# NODE_1_SCH.net
KiCad netlist of a schematic drawn in Altium Designer
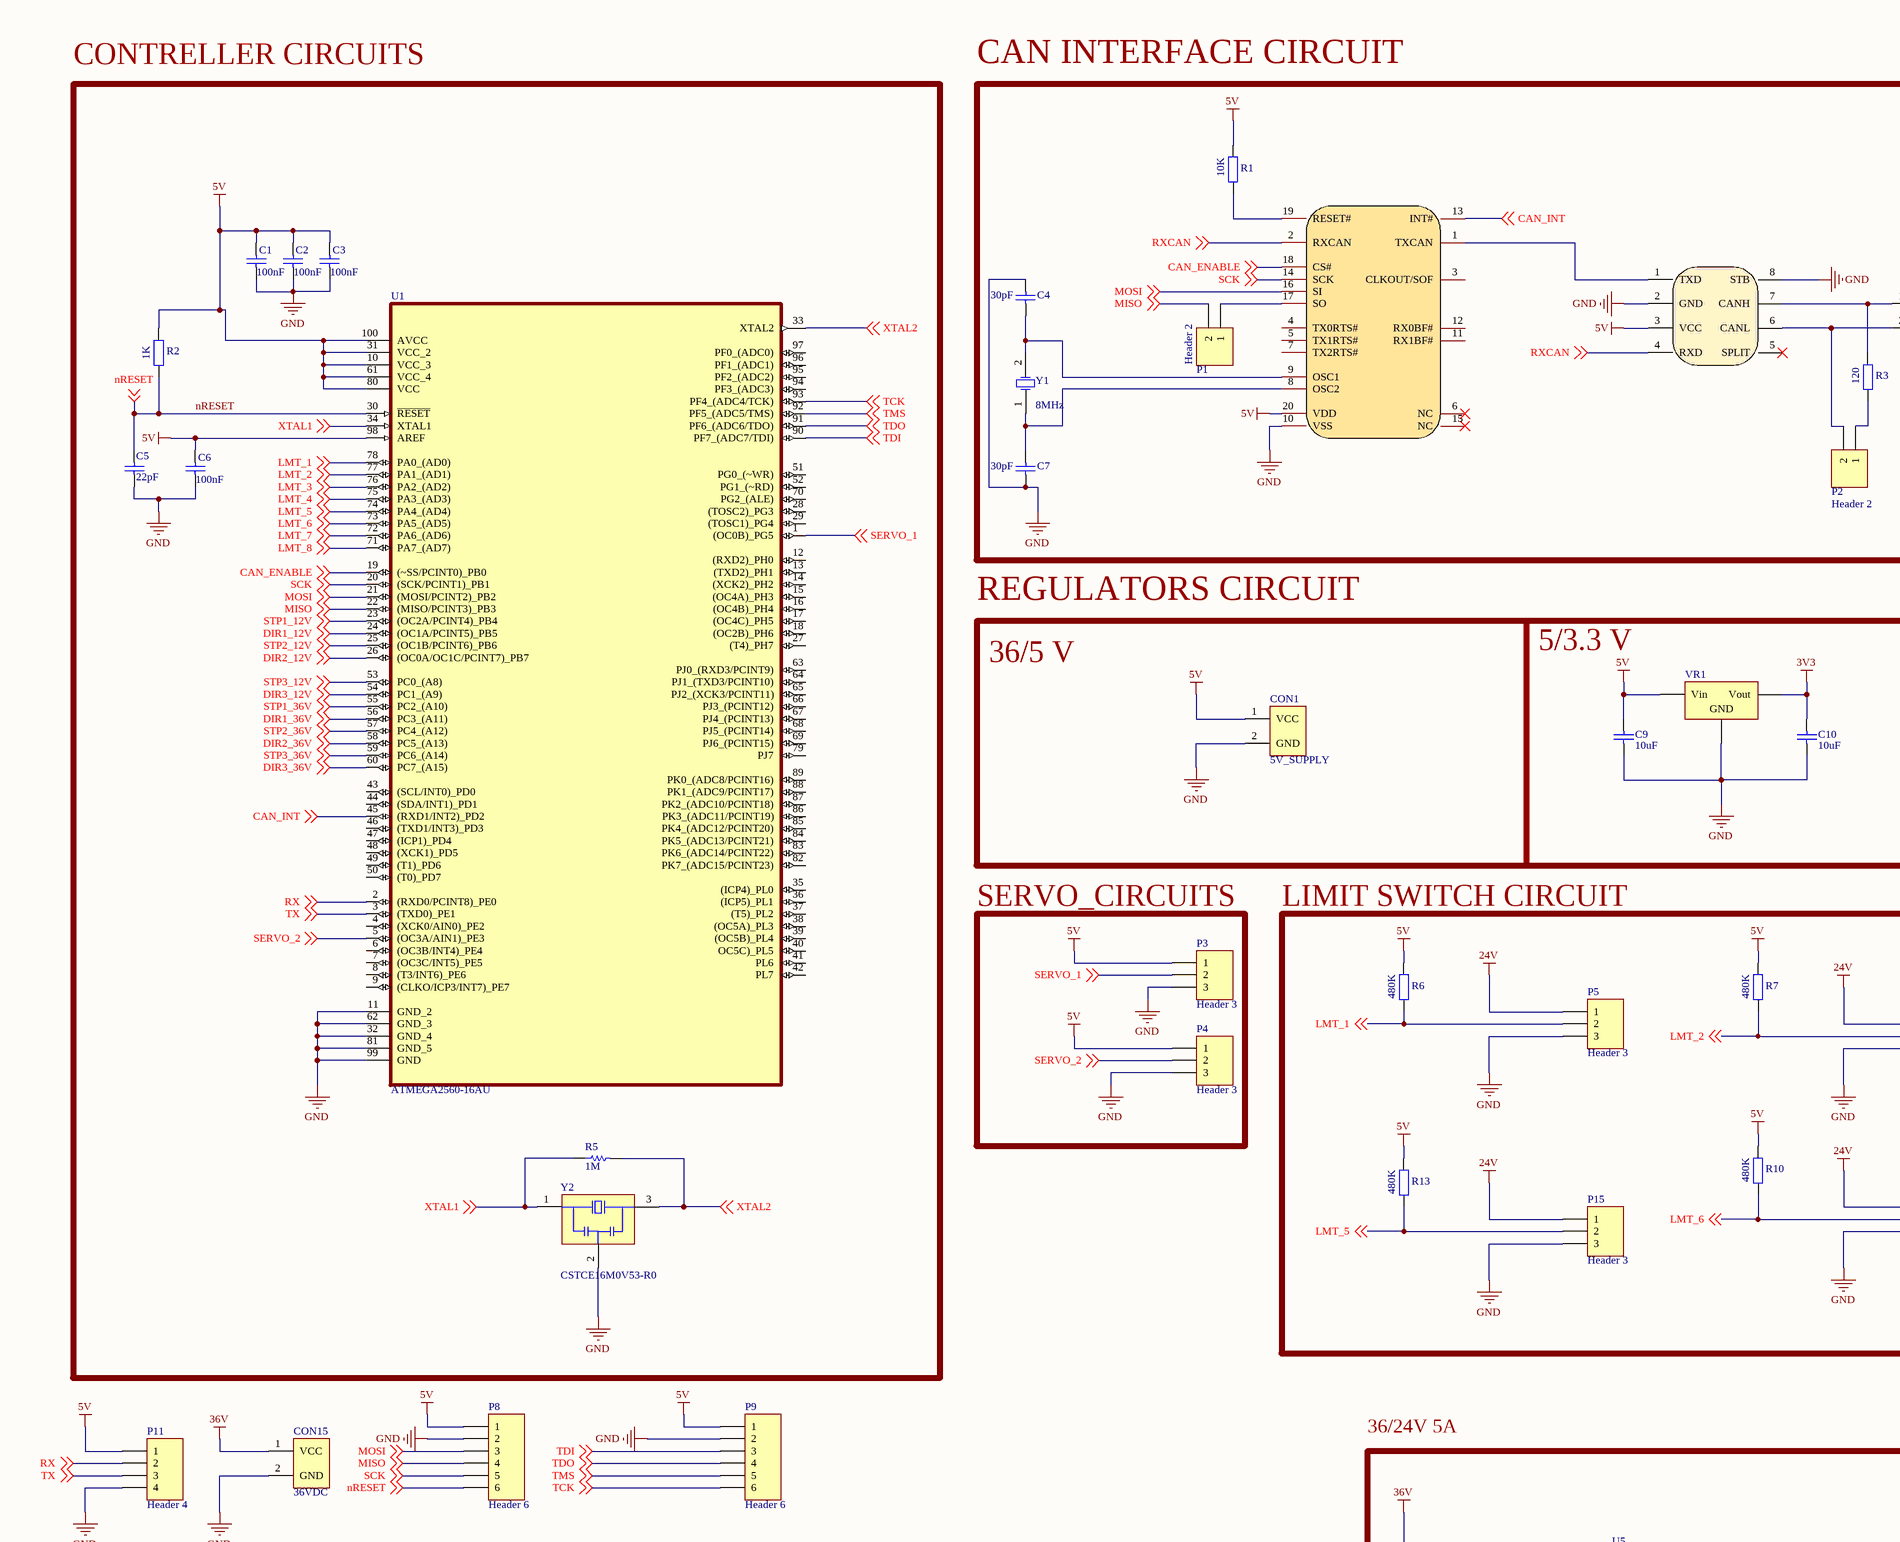
[diagram p0: NODE_1_SCH.SchDoc, top left]
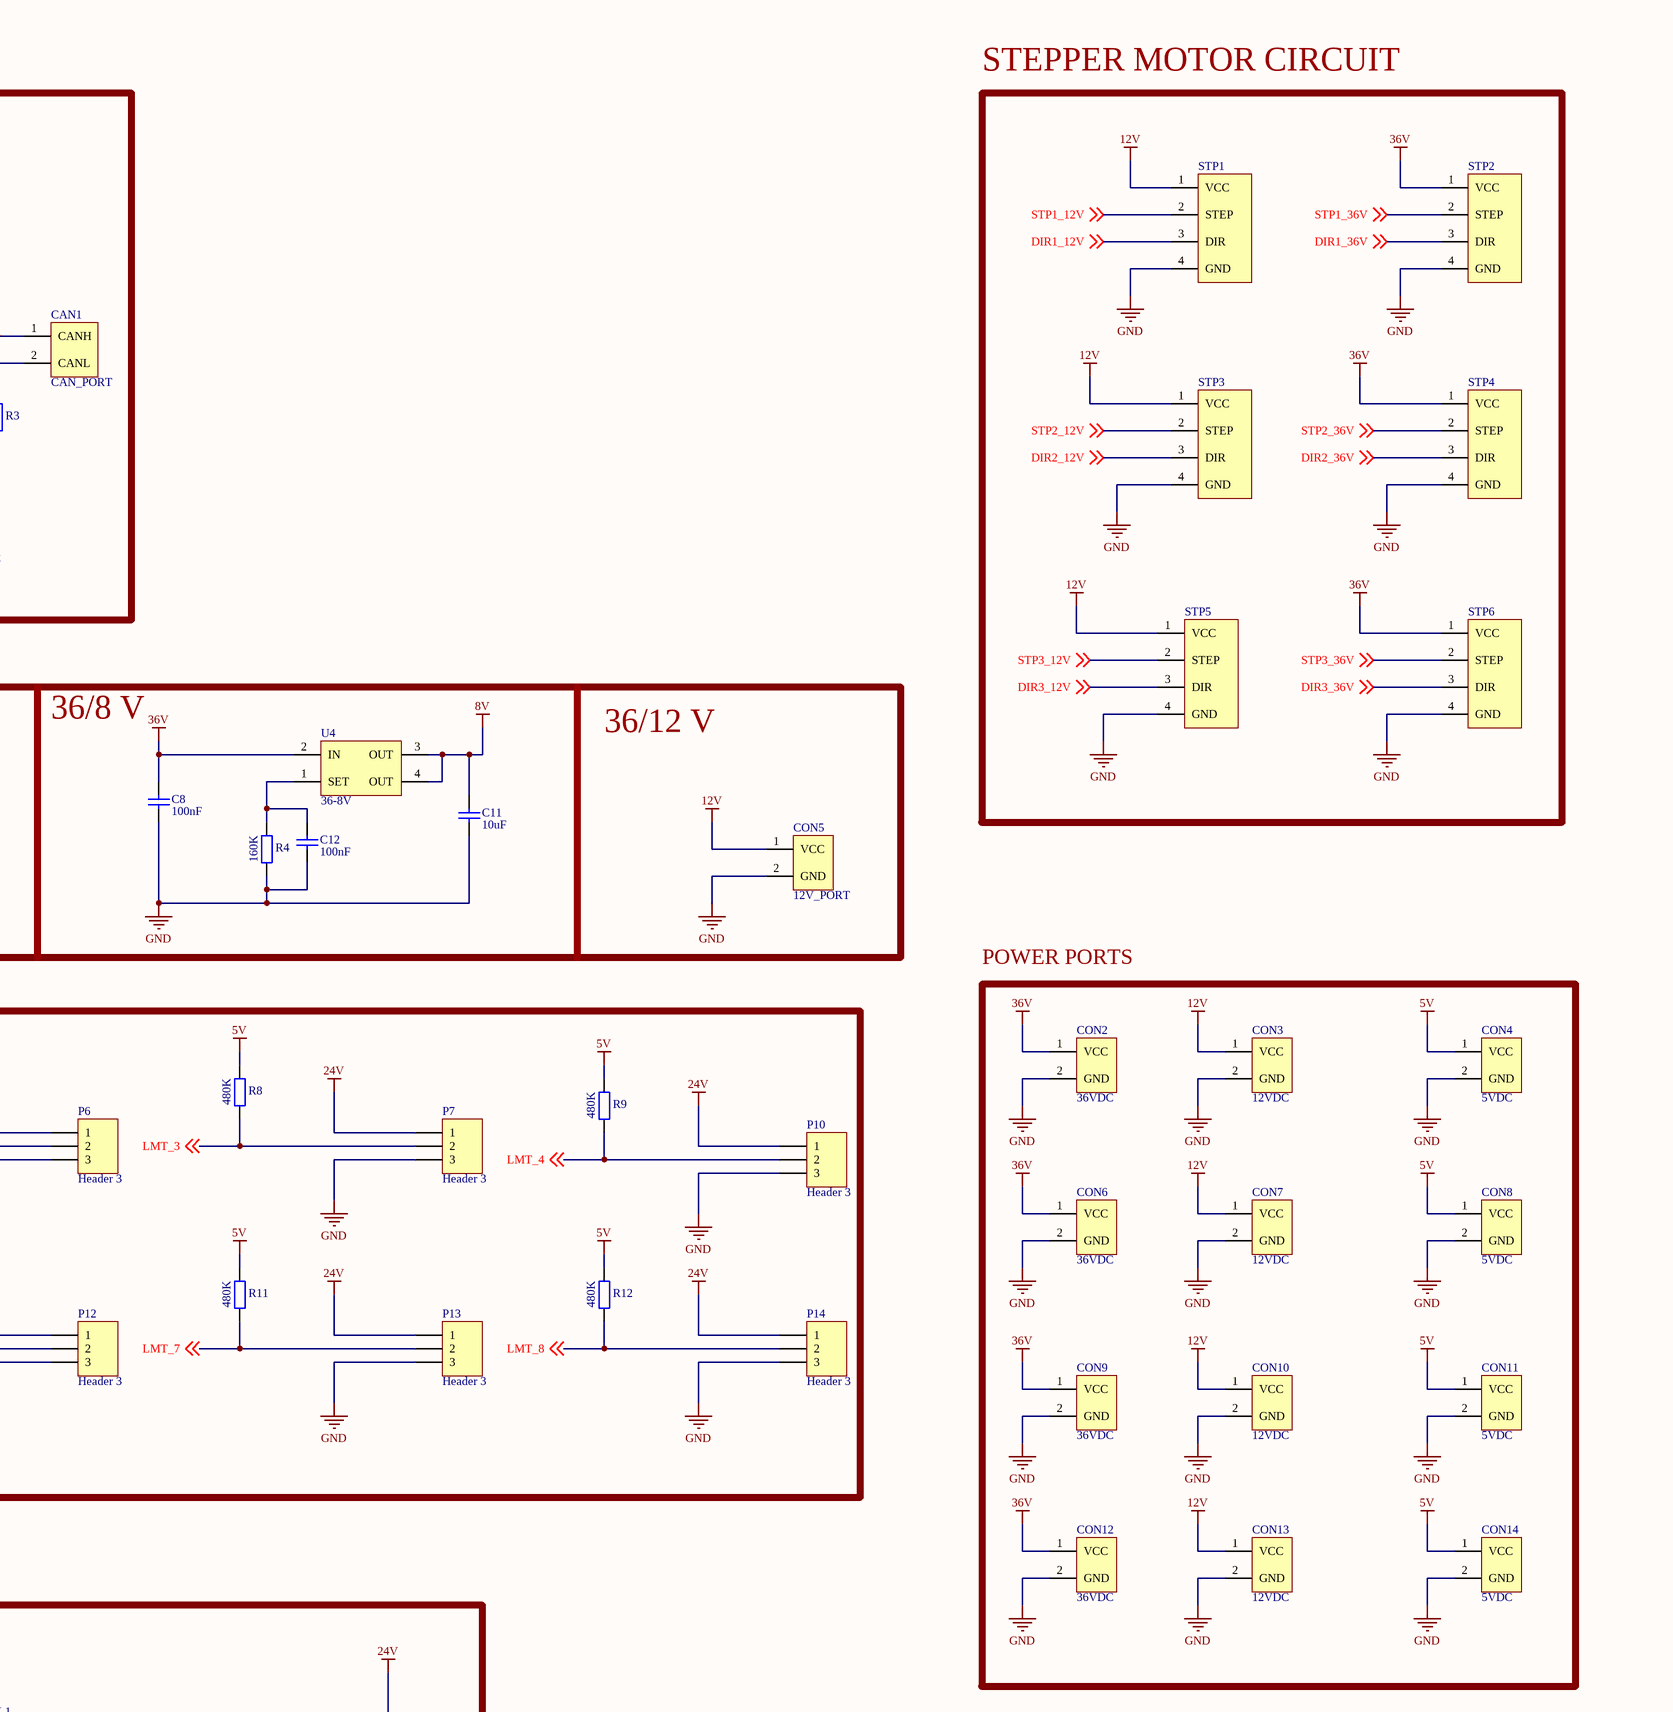
[diagram p1: NODE_1_SCH.SchDoc, top right]
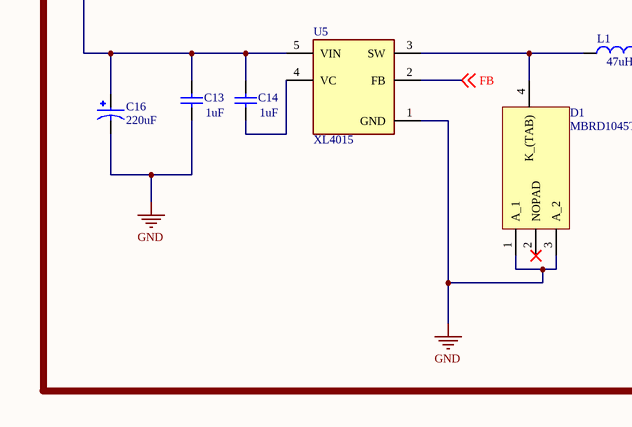
[diagram p2: NODE_1_SCH.SchDoc, bottom left]
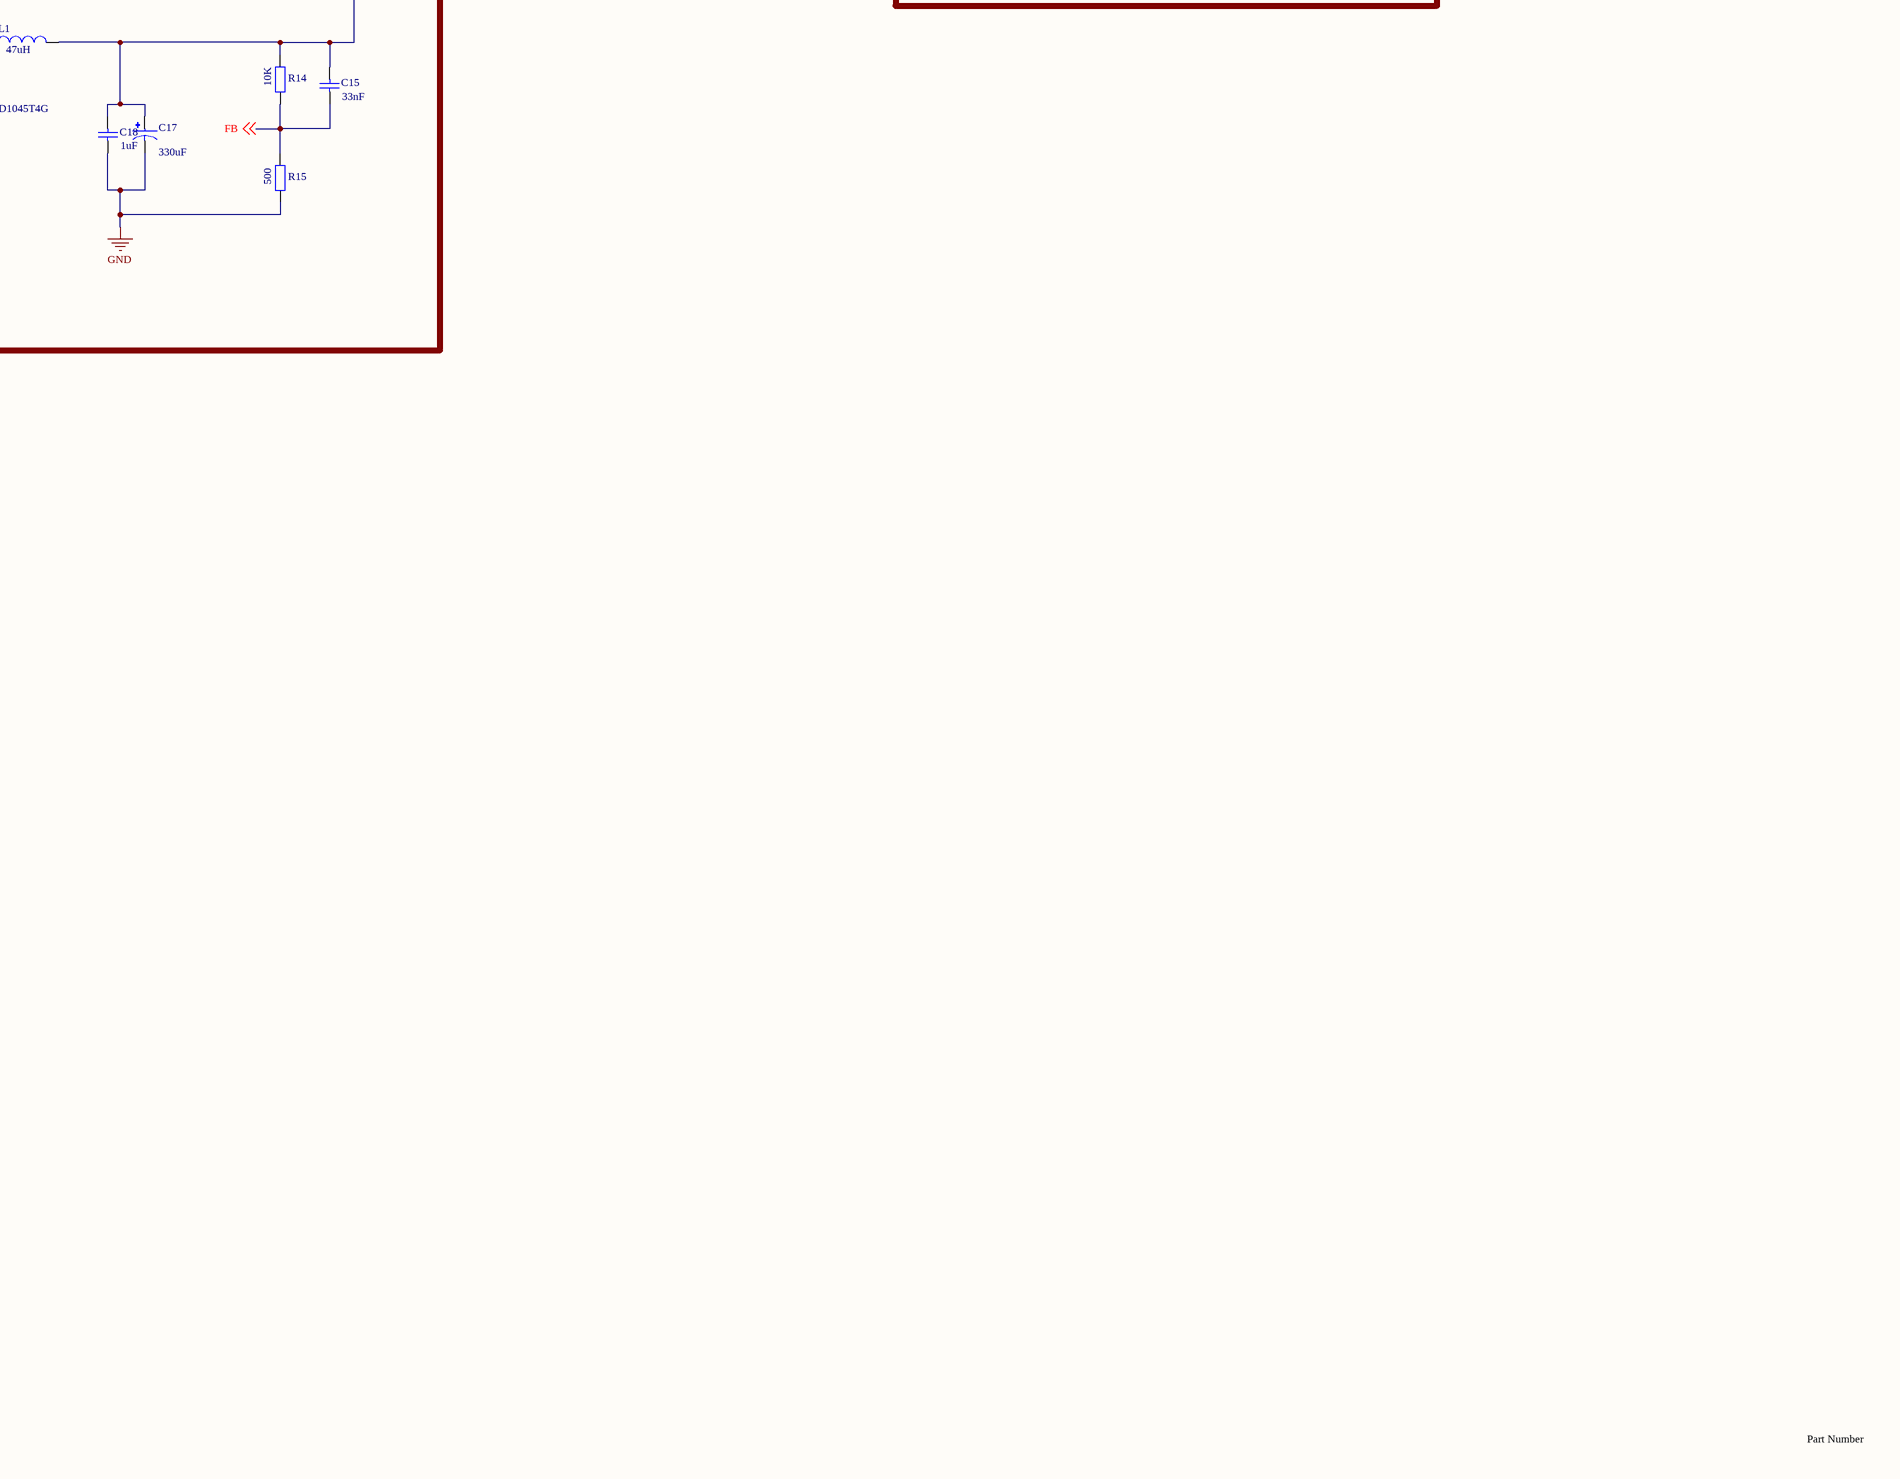
[diagram p3: NODE_1_SCH.SchDoc, bottom right]

(export (version "E")
  (design (tool "Eeschema 10.0.6"))
  (components
    (comp (ref "C1")
      (value "100nF")
      (footprint "CAPC2012X135N")
      (description "Capacitor")
      (fields
        (field (name "PART NUMBER") "TCC0805X7R104M500DT")
        (field (name "Comment") "Cap")
        (field (name "PUBLISHER") "Altium Limited")
      )
      (libsource (lib "Miscellaneous Devices") (part "Cap"))
    )
    (comp (ref "C2")
      (value "100nF")
      (footprint "CAPC2012X135N")
      (description "Capacitor")
      (fields
        (field (name "PART NUMBER") "TCC0805X7R104M500DT")
        (field (name "Comment") "Cap")
        (field (name "PUBLISHER") "Altium Limited")
      )
      (libsource (lib "Miscellaneous Devices") (part "Cap"))
    )
    (comp (ref "C3")
      (value "100nF")
      (footprint "CAPC2012X135N")
      (description "Capacitor")
      (fields
        (field (name "PART NUMBER") "TCC0805X7R104M500DT")
        (field (name "Comment") "Cap")
        (field (name "PUBLISHER") "Altium Limited")
      )
      (libsource (lib "Miscellaneous Devices") (part "Cap"))
    )
    (comp (ref "C4")
      (value "30pF")
      (footprint "CAPC2012X135N")
      (description "Capacitor")
      (fields
        (field (name "PART NUMBER") "TCC0805COG300J500BT")
        (field (name "Comment") "Cap")
        (field (name "PUBLISHER") "Altium Limited")
      )
      (libsource (lib "Miscellaneous Devices") (part "Cap"))
    )
    (comp (ref "C5")
      (value "22pF")
      (footprint "CAPC2012X135N")
      (description "Capacitor")
      (fields
        (field (name "PART NUMBER") "TCC0805COG220J500BT")
        (field (name "Comment") "Cap")
        (field (name "PUBLISHER") "Altium Limited")
      )
      (libsource (lib "Miscellaneous Devices") (part "Cap"))
    )
    (comp (ref "C6")
      (value "100nF")
      (footprint "RAD-0.3")
      (description "Capacitor")
      (fields (field (name "Comment") "Cap") (field (name "PUBLISHER") "Altium Limited"))
      (libsource (lib "Miscellaneous Devices") (part "Cap"))
    )
    (comp (ref "C7")
      (value "30pF")
      (footprint "CAPC2012X135N")
      (description "Capacitor")
      (fields
        (field (name "PART NUMBER") "TCC0805COG300J500BT")
        (field (name "Comment") "Cap")
        (field (name "PUBLISHER") "Altium Limited")
      )
      (libsource (lib "Miscellaneous Devices") (part "Cap"))
    )
    (comp (ref "C8")
      (value "100nF")
      (footprint "CAPC2012X135N")
      (description "Capacitor")
      (fields
        (field (name "PART NUMBER") "TCC0805X7R104M500DT")
        (field (name "Comment") "Cap")
        (field (name "PUBLISHER") "Altium Limited")
      )
      (libsource (lib "Miscellaneous Devices") (part "Cap"))
    )
    (comp (ref "C9")
      (value "10uF")
      (footprint "CAPC2012X135N")
      (description "Capacitor")
      (fields
        (field (name "PART NUMBER") "CL21A106KOQNNNE")
        (field (name "Comment") "Cap")
        (field (name "PUBLISHER") "Altium Limited")
      )
      (libsource (lib "Miscellaneous Devices") (part "Cap"))
    )
    (comp (ref "C10")
      (value "10uF")
      (footprint "CAPC2012X135N")
      (description "Capacitor")
      (fields
        (field (name "PART NUMBER") "CL21A106KOQNNNE")
        (field (name "Comment") "Cap")
        (field (name "PUBLISHER") "Altium Limited")
      )
      (libsource (lib "Miscellaneous Devices") (part "Cap"))
    )
    (comp (ref "C11")
      (value "10uF")
      (footprint "CAPC2012X135N")
      (description "Capacitor")
      (fields
        (field (name "PART NUMBER") "CL21A106KOQNNNE")
        (field (name "Comment") "Cap")
        (field (name "PUBLISHER") "Altium Limited")
      )
      (libsource (lib "Miscellaneous Devices") (part "Cap"))
    )
    (comp (ref "C12")
      (value "100nF")
      (footprint "CAPC2012X135N")
      (description "Capacitor")
      (fields
        (field (name "PART NUMBER") "TCC0805X7R104M500DT")
        (field (name "Comment") "Cap")
        (field (name "PUBLISHER") "Altium Limited")
      )
      (libsource (lib "Miscellaneous Devices") (part "Cap"))
    )
    (comp (ref "C13")
      (value "1uF")
      (footprint "CAPC2012X135N")
      (description "Capacitor")
      (fields
        (field (name "PART NUMBER") "CL21B105KBFNNNE")
        (field (name "Comment") "Cap")
        (field (name "PUBLISHER") "Altium Limited")
      )
      (libsource (lib "Miscellaneous Devices") (part "Cap"))
    )
    (comp (ref "C14")
      (value "1uF")
      (footprint "CAPC2012X135N")
      (description "Capacitor")
      (fields
        (field (name "PART NUMBER") "CL21B105KBFNNNE")
        (field (name "Comment") "Cap")
        (field (name "PUBLISHER") "Altium Limited")
      )
      (libsource (lib "Miscellaneous Devices") (part "Cap"))
    )
    (comp (ref "C15")
      (value "33nF")
      (footprint "CAPC2012X135N")
      (description "Capacitor")
      (fields
        (field (name "PART NUMBER") "TCC0805X7R333M500DT")
        (field (name "Comment") "Cap")
        (field (name "PUBLISHER") "Altium Limited")
      )
      (libsource (lib "Miscellaneous Devices") (part "Cap"))
    )
    (comp (ref "C16")
      (value "220uF")
      (footprint "CAP_EEVTG1H221Q")
      (description "220ÂµF 50V Aluminum Electrolytic Capacitors Radial, Can - SMD 230mOhm @ 100kHz 2000 Hrs @ 125Â°C")
      (fields (field (name "MF") "Panasonic Electronic") (field (name "PART NUMBER") "EEV-TG1H221Q"))
      (libsource (lib "IOT_Library") (part "EEVTG1H221Q"))
    )
    (comp (ref "C17")
      (value "330uF")
      (footprint "CAP_EEEFN1E331V")
      (description "CAP ALUM 330UF 20% 25V SMD")
      (fields (field (name "MF") "Panasonic") (field (name "DIGI-KEY_PART_NUMBER") "10-EEE-FN1E331VTR-ND"))
      (libsource (lib "IOT_Library") (part "EEEFN1E331V"))
    )
    (comp (ref "C18")
      (value "1uF")
      (footprint "CAPC2012X135N")
      (description "Capacitor")
      (fields
        (field (name "PART NUMBER") "CL21B105KBFNNNE")
        (field (name "Comment") "Cap")
        (field (name "PUBLISHER") "Altium Limited")
      )
      (libsource (lib "Miscellaneous Devices") (part "Cap"))
    )
    (comp (ref "CAN1")
      (value "CAN_PORT")
      (footprint "12V_CON")
      (fields (field (name "PART NUMBER") "MX126-5.0-02P-GN01-Cu-S-A"))
      (libsource (lib "IOT_Library") (part "2PIN_CON_1"))
    )
    (comp (ref "CON1")
      (value "5V_SUPPLY")
      (footprint "12V_CON")
      (fields (field (name "PART NUMBER") "MX126-5.0-02P-GN01-Cu-S-A"))
      (libsource (lib "IOT_Library") (part "2PIN_CON"))
    )
    (comp (ref "CON2")
      (value "36VDC")
      (footprint "12V_CON")
      (fields (field (name "PART NUMBER") "MX126-5.0-02P-GN01-Cu-S-A"))
      (libsource (lib "IOT_Library") (part "2PIN_CON_2"))
    )
    (comp (ref "CON3")
      (value "12VDC")
      (footprint "12V_CON")
      (fields (field (name "PART NUMBER") "MX126-5.0-02P-GN01-Cu-S-A"))
      (libsource (lib "IOT_Library") (part "2PIN_CON_2"))
    )
    (comp (ref "CON4")
      (value "5VDC")
      (footprint "12V_CON")
      (fields (field (name "PART NUMBER") "MX126-5.0-02P-GN01-Cu-S-A"))
      (libsource (lib "IOT_Library") (part "2PIN_CON_2"))
    )
    (comp (ref "CON5")
      (value "12V_PORT")
      (footprint "12V_CON")
      (fields (field (name "PART NUMBER") "MX126-5.0-02P-GN01-Cu-S-A"))
      (libsource (lib "IOT_Library") (part "2PIN_CON"))
    )
    (comp (ref "CON6")
      (value "36VDC")
      (footprint "12V_CON")
      (fields (field (name "PART NUMBER") "MX126-5.0-02P-GN01-Cu-S-A"))
      (libsource (lib "IOT_Library") (part "2PIN_CON_2"))
    )
    (comp (ref "CON7")
      (value "12VDC")
      (footprint "12V_CON")
      (fields (field (name "PART NUMBER") "MX126-5.0-02P-GN01-Cu-S-A"))
      (libsource (lib "IOT_Library") (part "2PIN_CON_2"))
    )
    (comp (ref "CON8")
      (value "5VDC")
      (footprint "12V_CON")
      (fields (field (name "PART NUMBER") "MX126-5.0-02P-GN01-Cu-S-A"))
      (libsource (lib "IOT_Library") (part "2PIN_CON_2"))
    )
    (comp (ref "CON9")
      (value "36VDC")
      (footprint "12V_CON")
      (fields (field (name "PART NUMBER") "MX126-5.0-02P-GN01-Cu-S-A"))
      (libsource (lib "IOT_Library") (part "2PIN_CON_2"))
    )
    (comp (ref "CON10")
      (value "12VDC")
      (footprint "12V_CON")
      (fields (field (name "PART NUMBER") "MX126-5.0-02P-GN01-Cu-S-A"))
      (libsource (lib "IOT_Library") (part "2PIN_CON_2"))
    )
    (comp (ref "CON11")
      (value "5VDC")
      (footprint "12V_CON")
      (fields (field (name "PART NUMBER") "MX126-5.0-02P-GN01-Cu-S-A"))
      (libsource (lib "IOT_Library") (part "2PIN_CON_2"))
    )
    (comp (ref "CON12")
      (value "36VDC")
      (footprint "12V_CON")
      (fields (field (name "PART NUMBER") "MX126-5.0-02P-GN01-Cu-S-A"))
      (libsource (lib "IOT_Library") (part "2PIN_CON_2"))
    )
    (comp (ref "CON13")
      (value "12VDC")
      (footprint "12V_CON")
      (fields (field (name "PART NUMBER") "MX126-5.0-02P-GN01-Cu-S-A"))
      (libsource (lib "IOT_Library") (part "2PIN_CON_2"))
    )
    (comp (ref "CON14")
      (value "5VDC")
      (footprint "12V_CON")
      (fields (field (name "PART NUMBER") "MX126-5.0-02P-GN01-Cu-S-A"))
      (libsource (lib "IOT_Library") (part "2PIN_CON_2"))
    )
    (comp (ref "CON15")
      (value "36VDC")
      (footprint "12V_CON")
      (fields (field (name "PART NUMBER") "MX126-5.0-02P-GN01-Cu-S-A"))
      (libsource (lib "IOT_Library") (part "2PIN_CON_2"))
    )
    (comp (ref "D1")
      (value "MBRD1045T4G")
      (footprint "TO229P990X238-4N")
      (description "Diode Schottky 45V 10A Surface Mount DPAK")
      (fields (field (name "MF") "ON Semiconductor"))
      (libsource (lib "IOT_Library") (part "MBRD1045T4G"))
    )
    (comp (ref "L1")
      (value "47uH")
      (footprint "IND_MWSA1206S_SNL")
      (description "Inductor")
      (fields (field (name "PART NUMBER") "MWSA1206S-470MT") (field (name "PUBLISHER") "Altium Limited"))
      (libsource (lib "Miscellaneous Devices") (part "Inductor"))
    )
    (comp (ref "P1")
      (value "Header 2")
      (footprint "SAMTEC_TS-102-G-A")
      (description "Header, 2-Pin")
      (fields (field (name "PART NUMBER") "PH-01078") (field (name "PUBLISHER") "Altium Limited"))
      (libsource (lib "Miscellaneous Connectors") (part "Header 2"))
    )
    (comp (ref "P2")
      (value "Header 2")
      (footprint "SAMTEC_TS-102-G-A")
      (description "Header, 2-Pin")
      (fields (field (name "PART NUMBER") "PH-01078") (field (name "PUBLISHER") "Altium Limited"))
      (libsource (lib "Miscellaneous Connectors") (part "Header 2"))
    )
    (comp (ref "P3")
      (value "Header 3")
      (footprint "3PIN_H")
      (description "Header, 3-Pin")
      (fields (field (name "PART NUMBER") "DB125-3.81-3P-BK-S") (field (name "PUBLISHER") "Altium Limited"))
      (libsource (lib "Miscellaneous Connectors") (part "Header 3"))
    )
    (comp (ref "P4")
      (value "Header 3")
      (footprint "3PIN_H")
      (description "Header, 3-Pin")
      (fields (field (name "PART NUMBER") "DB125-3.81-3P-BK-S") (field (name "PUBLISHER") "Altium Limited"))
      (libsource (lib "Miscellaneous Connectors") (part "Header 3"))
    )
    (comp (ref "P5")
      (value "Header 3")
      (footprint "3PIN_H")
      (description "Header, 3-Pin")
      (fields (field (name "PART NUMBER") "DB125-3.81-3P-BK-S") (field (name "PUBLISHER") "Altium Limited"))
      (libsource (lib "Miscellaneous Connectors") (part "Header 3"))
    )
    (comp (ref "P6")
      (value "Header 3")
      (footprint "3PIN_H")
      (description "Header, 3-Pin")
      (fields (field (name "PART NUMBER") "DB125-3.81-3P-BK-S") (field (name "PUBLISHER") "Altium Limited"))
      (libsource (lib "Miscellaneous Connectors") (part "Header 3"))
    )
    (comp (ref "P7")
      (value "Header 3")
      (footprint "3PIN_H")
      (description "Header, 3-Pin")
      (fields (field (name "PART NUMBER") "DB125-3.81-3P-BK-S") (field (name "PUBLISHER") "Altium Limited"))
      (libsource (lib "Miscellaneous Connectors") (part "Header 3"))
    )
    (comp (ref "P8")
      (value "Header 6")
      (footprint "HDR1X6")
      (description "Header, 6-Pin")
      (fields (field (name "PART NUMBER") "HB-PH3-25414PB2GOP") (field (name "PUBLISHER") "Altium Limited"))
      (libsource (lib "Miscellaneous Connectors") (part "Header 6"))
    )
    (comp (ref "P9")
      (value "Header 6")
      (footprint "HDR1X6")
      (description "Header, 6-Pin")
      (fields (field (name "PART NUMBER") "HB-PH3-25414PB2GOP") (field (name "PUBLISHER") "Altium Limited"))
      (libsource (lib "Miscellaneous Connectors") (part "Header 6"))
    )
    (comp (ref "P10")
      (value "Header 3")
      (footprint "3PIN_H")
      (description "Header, 3-Pin")
      (fields (field (name "PART NUMBER") "DB125-3.81-3P-BK-S") (field (name "PUBLISHER") "Altium Limited"))
      (libsource (lib "Miscellaneous Connectors") (part "Header 3"))
    )
    (comp (ref "P11")
      (value "Header 4")
      (footprint "HDR1X4")
      (description "Header, 4-Pin")
      (fields (field (name "PART NUMBER") "P125-1106A0BS116A1") (field (name "PUBLISHER") "Altium Limited"))
      (libsource (lib "Miscellaneous Connectors") (part "Header 4"))
    )
    (comp (ref "P12")
      (value "Header 3")
      (footprint "3PIN_H")
      (description "Header, 3-Pin")
      (fields (field (name "PART NUMBER") "DB125-3.81-3P-BK-S") (field (name "PUBLISHER") "Altium Limited"))
      (libsource (lib "Miscellaneous Connectors") (part "Header 3"))
    )
    (comp (ref "P13")
      (value "Header 3")
      (footprint "3PIN_H")
      (description "Header, 3-Pin")
      (fields (field (name "PART NUMBER") "DB125-3.81-3P-BK-S") (field (name "PUBLISHER") "Altium Limited"))
      (libsource (lib "Miscellaneous Connectors") (part "Header 3"))
    )
    (comp (ref "P14")
      (value "Header 3")
      (footprint "3PIN_H")
      (description "Header, 3-Pin")
      (fields (field (name "PART NUMBER") "DB125-3.81-3P-BK-S") (field (name "PUBLISHER") "Altium Limited"))
      (libsource (lib "Miscellaneous Connectors") (part "Header 3"))
    )
    (comp (ref "P15")
      (value "Header 3")
      (footprint "3PIN_H")
      (description "Header, 3-Pin")
      (fields (field (name "PART NUMBER") "DB125-3.81-3P-BK-S") (field (name "PUBLISHER") "Altium Limited"))
      (libsource (lib "Miscellaneous Connectors") (part "Header 3"))
    )
    (comp (ref "R1")
      (value "10K")
      (footprint "RESC2013X06N")
      (description "Resistor")
      (fields
        (field (name "PART NUMBER") "RC0805JR-0710KL")
        (field (name "Comment") "Res2")
        (field (name "PUBLISHER") "Altium Limited")
      )
      (libsource (lib "Miscellaneous Devices") (part "Res2"))
    )
    (comp (ref "R2")
      (value "1K")
      (footprint "RESC2013X06N")
      (description "Resistor")
      (fields
        (field (name "PART NUMBER") "0805W8J0102T5E")
        (field (name "Comment") "Res2")
        (field (name "PUBLISHER") "Altium Limited")
      )
      (libsource (lib "Miscellaneous Devices") (part "Res2"))
    )
    (comp (ref "R3")
      (value "120")
      (footprint "CRCW1206120RFKEAHP")
      (description "Resistor")
      (fields
        (field (name "PART NUMBER") "CRCW1206120RFKEAHP")
        (field (name "Comment") "Res2")
        (field (name "PUBLISHER") "Altium Limited")
      )
      (libsource (lib "Miscellaneous Devices") (part "Res2"))
    )
    (comp (ref "R4")
      (value "160K")
      (footprint "RESC2013X06N")
      (description "Resistor")
      (fields
        (field (name "PART NUMBER") "RTT05164JTP")
        (field (name "Comment") "Res2")
        (field (name "PUBLISHER") "Altium Limited")
      )
      (libsource (lib "Miscellaneous Devices") (part "Res2"))
    )
    (comp (ref "R5")
      (value "1M")
      (footprint "RESC2013X06N")
      (description "Resistor")
      (fields
        (field (name "PART NUMBER") "RC0805JR-071KL")
        (field (name "Comment") "R1M")
        (field (name "PUBLISHER") "Altium Limited")
      )
      (libsource (lib "Miscellaneous Devices") (part "Res1"))
    )
    (comp (ref "R6")
      (value "480K")
      (footprint "CRCW1206120RFKEAHP")
      (description "Resistor")
      (fields
        (field (name "PART NUMBER") "1206W4J0484T5E")
        (field (name "Comment") "Res2")
        (field (name "PUBLISHER") "Altium Limited")
      )
      (libsource (lib "Miscellaneous Devices") (part "Res2"))
    )
    (comp (ref "R7")
      (value "480K")
      (footprint "CRCW1206120RFKEAHP")
      (description "Resistor")
      (fields
        (field (name "PART NUMBER") "1206W4J0484T5E")
        (field (name "Comment") "Res2")
        (field (name "PUBLISHER") "Altium Limited")
      )
      (libsource (lib "Miscellaneous Devices") (part "Res2"))
    )
    (comp (ref "R8")
      (value "480K")
      (footprint "CRCW1206120RFKEAHP")
      (description "Resistor")
      (fields
        (field (name "PART NUMBER") "1206W4J0484T5E")
        (field (name "Comment") "Res2")
        (field (name "PUBLISHER") "Altium Limited")
      )
      (libsource (lib "Miscellaneous Devices") (part "Res2"))
    )
    (comp (ref "R9")
      (value "480K")
      (footprint "CRCW1206120RFKEAHP")
      (description "Resistor")
      (fields
        (field (name "PART NUMBER") "1206W4J0484T5E")
        (field (name "Comment") "Res2")
        (field (name "PUBLISHER") "Altium Limited")
      )
      (libsource (lib "Miscellaneous Devices") (part "Res2"))
    )
    (comp (ref "R10")
      (value "480K")
      (footprint "CRCW1206120RFKEAHP")
      (description "Resistor")
      (fields
        (field (name "PART NUMBER") "1206W4J0484T5E")
        (field (name "Comment") "Res2")
        (field (name "PUBLISHER") "Altium Limited")
      )
      (libsource (lib "Miscellaneous Devices") (part "Res2"))
    )
    (comp (ref "R11")
      (value "480K")
      (footprint "CRCW1206120RFKEAHP")
      (description "Resistor")
      (fields
        (field (name "PART NUMBER") "1206W4J0484T5E")
        (field (name "Comment") "Res2")
        (field (name "PUBLISHER") "Altium Limited")
      )
      (libsource (lib "Miscellaneous Devices") (part "Res2"))
    )
    (comp (ref "R12")
      (value "480K")
      (footprint "CRCW1206120RFKEAHP")
      (description "Resistor")
      (fields
        (field (name "PART NUMBER") "1206W4J0484T5E")
        (field (name "Comment") "Res2")
        (field (name "PUBLISHER") "Altium Limited")
      )
      (libsource (lib "Miscellaneous Devices") (part "Res2"))
    )
    (comp (ref "R13")
      (value "480K")
      (footprint "CRCW1206120RFKEAHP")
      (description "Resistor")
      (fields
        (field (name "PART NUMBER") "1206W4J0484T5E")
        (field (name "Comment") "Res2")
        (field (name "PUBLISHER") "Altium Limited")
      )
      (libsource (lib "Miscellaneous Devices") (part "Res2"))
    )
    (comp (ref "R14")
      (value "10K")
      (footprint "RESC2013X06N")
      (description "Resistor")
      (fields
        (field (name "PART NUMBER") "RC0805JR-0710KL")
        (field (name "Comment") "Res2")
        (field (name "PUBLISHER") "Altium Limited")
      )
      (libsource (lib "Miscellaneous Devices") (part "Res2"))
    )
    (comp (ref "R15")
      (value "500")
      (footprint "RESC2013X06N")
      (description "Resistor")
      (fields
        (field (name "PART NUMBER") "ARG05FTC5000")
        (field (name "Comment") "Res2")
        (field (name "PUBLISHER") "Altium Limited")
      )
      (libsource (lib "Miscellaneous Devices") (part "Res2"))
    )
    (comp (ref "STP1")
      (value "STPR_MTR_PORT")
      (footprint "CONN-TH_4P-P5.08_DIBO_DB128V-5.08 - duplicate1")
      (description "OUTPUT TO SUPPLY THE STEPPER MOTOR NEEDS")
      (fields (field (name "PART NUMBER") "WJ500V-5.08-2P"))
      (libsource (lib "IOT_Library") (part "STPR_MTR_PORT"))
    )
    (comp (ref "STP2")
      (value "STPR_MTR_PORT")
      (footprint "CONN-TH_4P-P5.08_DIBO_DB128V-5.08 - duplicate1")
      (description "OUTPUT TO SUPPLY THE STEPPER MOTOR NEEDS")
      (fields (field (name "PART NUMBER") "WJ500V-5.08-2P"))
      (libsource (lib "IOT_Library") (part "STPR_MTR_PORT"))
    )
    (comp (ref "STP3")
      (value "STPR_MTR_PORT")
      (footprint "CONN-TH_4P-P5.08_DIBO_DB128V-5.08 - duplicate1")
      (description "OUTPUT TO SUPPLY THE STEPPER MOTOR NEEDS")
      (fields (field (name "PART NUMBER") "WJ500V-5.08-2P"))
      (libsource (lib "IOT_Library") (part "STPR_MTR_PORT"))
    )
    (comp (ref "STP4")
      (value "STPR_MTR_PORT")
      (footprint "CONN-TH_4P-P5.08_DIBO_DB128V-5.08 - duplicate1")
      (description "OUTPUT TO SUPPLY THE STEPPER MOTOR NEEDS")
      (fields (field (name "PART NUMBER") "WJ500V-5.08-2P"))
      (libsource (lib "IOT_Library") (part "STPR_MTR_PORT"))
    )
    (comp (ref "STP5")
      (value "STPR_MTR_PORT")
      (footprint "CONN-TH_4P-P5.08_DIBO_DB128V-5.08 - duplicate1")
      (description "OUTPUT TO SUPPLY THE STEPPER MOTOR NEEDS")
      (fields (field (name "PART NUMBER") "WJ500V-5.08-2P"))
      (libsource (lib "IOT_Library") (part "STPR_MTR_PORT"))
    )
    (comp (ref "STP6")
      (value "STPR_MTR_PORT")
      (footprint "CONN-TH_4P-P5.08_DIBO_DB128V-5.08 - duplicate1")
      (description "OUTPUT TO SUPPLY THE STEPPER MOTOR NEEDS")
      (fields (field (name "PART NUMBER") "WJ500V-5.08-2P"))
      (libsource (lib "IOT_Library") (part "STPR_MTR_PORT"))
    )
    (comp (ref "U1")
      (value "ATMEGA2560-16AU")
      (footprint "QFP50P1600X1600X120-100N")
      (description "AVR AVRÂ® ATmega Microcontroller IC 8-Bit 16MHz 256KB (128K x 16) FLASH 100-TQFP (14x14)")
      (fields (field (name "MF") "Microchip"))
      (libsource (lib "IOT_Library") (part "ATMEGA2560-16AU"))
    )
    (comp (ref "U2")
      (value "TJA1050DRG")
      (footprint "SOP-8_L4.9-W3.9-P1.27-LS6.0-BL")
      (fields (field (name "MANUFACTURER") "HGC(深圳汉芯)"))
      (libsource (lib "IOT_Library") (part "TJA1050DRG"))
    )
    (comp (ref "U3")
      (value "MCP2515T-I/ST")
      (footprint "TSSOP-20_L6.5-W4.4-P0.65-LS6.4-BL")
      (fields (field (name "MANUFACTURER") "MICROCHIP(美国微芯)"))
      (libsource (lib "IOT_Library") (part "MCP2515T-I/ST"))
    )
    (comp (ref "U4")
      (value "36-8V")
      (footprint "SOT-223-3_L6.5-W3.4-P2.30-LS7.0-BR")
      (description "LDO Regulator Pos 0V to 34.5V 0.8A Automotive 4-Pin(3+Tab) SOT-223 Tube")
      (fields
        (field (name "MANUFACTURER") "Analog Devices / Linear Technology")
        (field (name "PART NUMBER") "LT3088MPST#PBF")
      )
      (libsource (lib "IOT_Library") (part "LT3088MPST#PBF"))
    )
    (comp (ref "U5")
      (value "XL4015")
      (footprint "CONV_XL4015")
      (description "5A 180KHz 36V Buck DC to DC Converter")
      (fields (field (name "PART NUMBER") "XL4015E1"))
      (libsource (lib "IOT_Library") (part "XL4015"))
    )
    (comp (ref "VR1")
      (value "~")
      (footprint "DPAK-3_L6.6-W6.1-P2.28-LS9.9-BR")
      (description "36-8V")
      (fields (field (name "PART NUMBER") "AP7363-33D-13") (field (name "PUBLISHER") "Altium Limited"))
      (libsource (lib "Miscellaneous Devices") (part "Volt Reg"))
    )
    (comp (ref "Y1")
      (value "8MHz")
      (footprint "CRYSTAL-SMD_L7.4-W4.0-LS8.0")
      (description "Crystal Oscillator")
      (fields
        (field (name "PART NUMBER") "S47SMD8.000M12PF20R30B3")
        (field (name "Comment") "XTAL")
        (field (name "PUBLISHER") "Altium Limited")
      )
      (libsource (lib "Miscellaneous Devices") (part "XTAL"))
    )
    (comp (ref "Y2")
      (value "CSTCE16M0V53-R0")
      (footprint "OSC_CSTCE16M0V53-R0")
      (description "16 MHz Ceramic Resonator Built in Capacitor 15 pF Â±0.3% -20Â°C ~ 80Â°C Surface Mount")
      (fields (field (name "MF") "Murata"))
      (libsource (lib "IOT_Library") (part "CSTCE16M0V53-R0"))
    )
  )
  (nets
    (net (code "1") (name "3V3") (class "Default")
      (node (ref "C10") (pin "2") (pinfunction "2_2") (pintype "passive"))
      (node (ref "VR1") (pin "3") (pinfunction "Vout_3") (pintype "passive"))
    )
    (net (code "2") (name "5V") (class "Default")
      (node (ref "C1") (pin "1") (pinfunction "1_1") (pintype "passive"))
      (node (ref "C2") (pin "1") (pinfunction "1_1") (pintype "passive"))
      (node (ref "C3") (pin "1") (pinfunction "1_1") (pintype "passive"))
      (node (ref "C6") (pin "1") (pinfunction "1_1") (pintype "passive"))
      (node (ref "C9") (pin "2") (pinfunction "2_2") (pintype "passive"))
      (node (ref "CON1") (pin "1") (pinfunction "VCC_1") (pintype "passive"))
      (node (ref "CON11") (pin "1") (pinfunction "VCC_1") (pintype "passive"))
      (node (ref "CON14") (pin "1") (pinfunction "VCC_1") (pintype "passive"))
      (node (ref "CON4") (pin "1") (pinfunction "VCC_1") (pintype "passive"))
      (node (ref "CON8") (pin "1") (pinfunction "VCC_1") (pintype "passive"))
      (node (ref "P11") (pin "1") (pinfunction "1_1") (pintype "passive"))
      (node (ref "P3") (pin "1") (pinfunction "1_1") (pintype "passive"))
      (node (ref "P4") (pin "1") (pinfunction "1_1") (pintype "passive"))
      (node (ref "P8") (pin "1") (pinfunction "1_1") (pintype "passive"))
      (node (ref "P9") (pin "1") (pinfunction "1_1") (pintype "passive"))
      (node (ref "R1") (pin "2") (pinfunction "2_2") (pintype "passive"))
      (node (ref "R10") (pin "2") (pinfunction "2_2") (pintype "passive"))
      (node (ref "R11") (pin "2") (pinfunction "2_2") (pintype "passive"))
      (node (ref "R12") (pin "2") (pinfunction "2_2") (pintype "passive"))
      (node (ref "R13") (pin "2") (pinfunction "2_2") (pintype "passive"))
      (node (ref "R2") (pin "2") (pinfunction "2_2") (pintype "passive"))
      (node (ref "R6") (pin "2") (pinfunction "2_2") (pintype "passive"))
      (node (ref "R7") (pin "2") (pinfunction "2_2") (pintype "passive"))
      (node (ref "R8") (pin "2") (pinfunction "2_2") (pintype "passive"))
      (node (ref "R9") (pin "2") (pinfunction "2_2") (pintype "passive"))
      (node (ref "U1") (pin "10") (pinfunction "VCC_3_10") (pintype "power_in"))
      (node (ref "U1") (pin "100") (pinfunction "AVCC_100") (pintype "power_in"))
      (node (ref "U1") (pin "31") (pinfunction "VCC_2_31") (pintype "power_in"))
      (node (ref "U1") (pin "61") (pinfunction "VCC_4_61") (pintype "power_in"))
      (node (ref "U1") (pin "80") (pinfunction "VCC_80") (pintype "power_in"))
      (node (ref "U1") (pin "98") (pinfunction "AREF_98") (pintype "input"))
      (node (ref "U2") (pin "3") (pinfunction "VCC_3") (pintype "passive"))
      (node (ref "U3") (pin "20") (pinfunction "VDD_20") (pintype "passive"))
      (node (ref "VR1") (pin "1") (pinfunction "Vin_1") (pintype "passive"))
    )
    (net (code "3") (name "8V") (class "Default")
      (node (ref "C11") (pin "2") (pinfunction "2_2") (pintype "passive"))
      (node (ref "U4") (pin "3") (pinfunction "OUT_3") (pintype "passive"))
      (node (ref "U4") (pin "4") (pinfunction "OUT_4") (pintype "passive"))
    )
    (net (code "4") (name "12V") (class "Default")
      (node (ref "CON10") (pin "1") (pinfunction "VCC_1") (pintype "passive"))
      (node (ref "CON13") (pin "1") (pinfunction "VCC_1") (pintype "passive"))
      (node (ref "CON3") (pin "1") (pinfunction "VCC_1") (pintype "passive"))
      (node (ref "CON5") (pin "1") (pinfunction "VCC_1") (pintype "passive"))
      (node (ref "CON7") (pin "1") (pinfunction "VCC_1") (pintype "passive"))
      (node (ref "STP1") (pin "1") (pinfunction "VCC_1") (pintype "passive"))
      (node (ref "STP3") (pin "1") (pinfunction "VCC_1") (pintype "passive"))
      (node (ref "STP5") (pin "1") (pinfunction "VCC_1") (pintype "passive"))
    )
    (net (code "5") (name "24V") (class "Default")
      (node (ref "C15") (pin "1") (pinfunction "1_1") (pintype "passive"))
      (node (ref "C17") (pin "1") (pinfunction "1_1") (pintype "passive"))
      (node (ref "C18") (pin "1") (pinfunction "1_1") (pintype "passive"))
      (node (ref "L1") (pin "2") (pinfunction "2_2") (pintype "passive"))
      (node (ref "P10") (pin "1") (pinfunction "1_1") (pintype "passive"))
      (node (ref "P12") (pin "1") (pinfunction "1_1") (pintype "passive"))
      (node (ref "P13") (pin "1") (pinfunction "1_1") (pintype "passive"))
      (node (ref "P14") (pin "1") (pinfunction "1_1") (pintype "passive"))
      (node (ref "P15") (pin "1") (pinfunction "1_1") (pintype "passive"))
      (node (ref "P5") (pin "1") (pinfunction "1_1") (pintype "passive"))
      (node (ref "P6") (pin "1") (pinfunction "1_1") (pintype "passive"))
      (node (ref "P7") (pin "1") (pinfunction "1_1") (pintype "passive"))
      (node (ref "R14") (pin "2") (pinfunction "2_2") (pintype "passive"))
    )
    (net (code "6") (name "36V") (class "Default")
      (node (ref "C13") (pin "1") (pinfunction "1_1") (pintype "passive"))
      (node (ref "C14") (pin "1") (pinfunction "1_1") (pintype "passive"))
      (node (ref "C16") (pin "1") (pinfunction "1_1") (pintype "passive"))
      (node (ref "C8") (pin "2") (pinfunction "2_2") (pintype "passive"))
      (node (ref "CON12") (pin "1") (pinfunction "VCC_1") (pintype "passive"))
      (node (ref "CON15") (pin "1") (pinfunction "VCC_1") (pintype "passive"))
      (node (ref "CON2") (pin "1") (pinfunction "VCC_1") (pintype "passive"))
      (node (ref "CON6") (pin "1") (pinfunction "VCC_1") (pintype "passive"))
      (node (ref "CON9") (pin "1") (pinfunction "VCC_1") (pintype "passive"))
      (node (ref "STP2") (pin "1") (pinfunction "VCC_1") (pintype "passive"))
      (node (ref "STP4") (pin "1") (pinfunction "VCC_1") (pintype "passive"))
      (node (ref "STP6") (pin "1") (pinfunction "VCC_1") (pintype "passive"))
      (node (ref "U4") (pin "2") (pinfunction "IN_2") (pintype "passive"))
      (node (ref "U5") (pin "5") (pinfunction "VIN_5") (pintype "passive"))
    )
    (net (code "7") (name "CAN_ENABLE") (class "Default")
      (node (ref "U1") (pin "19") (pinfunction "(~SS/PCINT0)_PB0_19") (pintype "bidirectional"))
      (node (ref "U3") (pin "18") (pinfunction "CS#_18") (pintype "passive"))
    )
    (net (code "8") (name "CAN_INT") (class "Default")
      (node (ref "U1") (pin "45") (pinfunction "(RXD1/INT2)_PD2_45") (pintype "bidirectional"))
      (node (ref "U3") (pin "13") (pinfunction "INT#_13") (pintype "passive"))
    )
    (net (code "9") (name "DIR1_12V") (class "Default")
      (node (ref "STP1") (pin "3") (pinfunction "DIR_3") (pintype "passive"))
      (node (ref "U1") (pin "24") (pinfunction "(OC1A/PCINT5)_PB5_24") (pintype "bidirectional"))
    )
    (net (code "10") (name "DIR1_36V") (class "Default")
      (node (ref "STP2") (pin "3") (pinfunction "DIR_3") (pintype "passive"))
      (node (ref "U1") (pin "56") (pinfunction "PC3_(A11)_56") (pintype "bidirectional"))
    )
    (net (code "11") (name "DIR2_12V") (class "Default")
      (node (ref "STP3") (pin "3") (pinfunction "DIR_3") (pintype "passive"))
      (node (ref "U1") (pin "26") (pinfunction "(OC0A/OC1C/PCINT7)_PB7_26") (pintype "bidirectional"))
    )
    (net (code "12") (name "DIR2_36V") (class "Default")
      (node (ref "STP4") (pin "3") (pinfunction "DIR_3") (pintype "passive"))
      (node (ref "U1") (pin "58") (pinfunction "PC5_(A13)_58") (pintype "bidirectional"))
    )
    (net (code "13") (name "DIR3_12V") (class "Default")
      (node (ref "STP5") (pin "3") (pinfunction "DIR_3") (pintype "passive"))
      (node (ref "U1") (pin "54") (pinfunction "PC1_(A9)_54") (pintype "bidirectional"))
    )
    (net (code "14") (name "DIR3_36V") (class "Default")
      (node (ref "STP6") (pin "3") (pinfunction "DIR_3") (pintype "passive"))
      (node (ref "U1") (pin "60") (pinfunction "PC7_(A15)_60") (pintype "bidirectional"))
    )
    (net (code "15") (name "FB") (class "Default")
      (node (ref "C15") (pin "2") (pinfunction "2_2") (pintype "passive"))
      (node (ref "R14") (pin "1") (pinfunction "1_1") (pintype "passive"))
      (node (ref "R15") (pin "2") (pinfunction "2_2") (pintype "passive"))
      (node (ref "U5") (pin "2") (pinfunction "FB_2") (pintype "passive"))
    )
    (net (code "16") (name "GND") (class "Default")
      (node (ref "C1") (pin "2") (pinfunction "2_2") (pintype "passive"))
      (node (ref "C10") (pin "1") (pinfunction "1_1") (pintype "passive"))
      (node (ref "C11") (pin "1") (pinfunction "1_1") (pintype "passive"))
      (node (ref "C12") (pin "1") (pinfunction "1_1") (pintype "passive"))
      (node (ref "C13") (pin "2") (pinfunction "2_2") (pintype "passive"))
      (node (ref "C16") (pin "2") (pinfunction "2_2") (pintype "passive"))
      (node (ref "C17") (pin "2") (pinfunction "2_2") (pintype "passive"))
      (node (ref "C18") (pin "2") (pinfunction "2_2") (pintype "passive"))
      (node (ref "C2") (pin "2") (pinfunction "2_2") (pintype "passive"))
      (node (ref "C3") (pin "2") (pinfunction "2_2") (pintype "passive"))
      (node (ref "C4") (pin "1") (pinfunction "1_1") (pintype "passive"))
      (node (ref "C5") (pin "2") (pinfunction "2_2") (pintype "passive"))
      (node (ref "C6") (pin "2") (pinfunction "2_2") (pintype "passive"))
      (node (ref "C7") (pin "2") (pinfunction "2_2") (pintype "passive"))
      (node (ref "C8") (pin "1") (pinfunction "1_1") (pintype "passive"))
      (node (ref "C9") (pin "1") (pinfunction "1_1") (pintype "passive"))
      (node (ref "CON1") (pin "2") (pinfunction "GND_2") (pintype "passive"))
      (node (ref "CON10") (pin "2") (pinfunction "GND_2") (pintype "passive"))
      (node (ref "CON11") (pin "2") (pinfunction "GND_2") (pintype "passive"))
      (node (ref "CON12") (pin "2") (pinfunction "GND_2") (pintype "passive"))
      (node (ref "CON13") (pin "2") (pinfunction "GND_2") (pintype "passive"))
      (node (ref "CON14") (pin "2") (pinfunction "GND_2") (pintype "passive"))
      (node (ref "CON15") (pin "2") (pinfunction "GND_2") (pintype "passive"))
      (node (ref "CON2") (pin "2") (pinfunction "GND_2") (pintype "passive"))
      (node (ref "CON3") (pin "2") (pinfunction "GND_2") (pintype "passive"))
      (node (ref "CON4") (pin "2") (pinfunction "GND_2") (pintype "passive"))
      (node (ref "CON5") (pin "2") (pinfunction "GND_2") (pintype "passive"))
      (node (ref "CON6") (pin "2") (pinfunction "GND_2") (pintype "passive"))
      (node (ref "CON7") (pin "2") (pinfunction "GND_2") (pintype "passive"))
      (node (ref "CON8") (pin "2") (pinfunction "GND_2") (pintype "passive"))
      (node (ref "CON9") (pin "2") (pinfunction "GND_2") (pintype "passive"))
      (node (ref "D1") (pin "1") (pinfunction "A_1_1") (pintype "passive"))
      (node (ref "D1") (pin "3") (pinfunction "A_2_3") (pintype "passive"))
      (node (ref "P10") (pin "3") (pinfunction "3_3") (pintype "passive"))
      (node (ref "P11") (pin "4") (pinfunction "4_4") (pintype "passive"))
      (node (ref "P12") (pin "3") (pinfunction "3_3") (pintype "passive"))
      (node (ref "P13") (pin "3") (pinfunction "3_3") (pintype "passive"))
      (node (ref "P14") (pin "3") (pinfunction "3_3") (pintype "passive"))
      (node (ref "P15") (pin "3") (pinfunction "3_3") (pintype "passive"))
      (node (ref "P3") (pin "3") (pinfunction "3_3") (pintype "passive"))
      (node (ref "P4") (pin "3") (pinfunction "3_3") (pintype "passive"))
      (node (ref "P5") (pin "3") (pinfunction "3_3") (pintype "passive"))
      (node (ref "P6") (pin "3") (pinfunction "3_3") (pintype "passive"))
      (node (ref "P7") (pin "3") (pinfunction "3_3") (pintype "passive"))
      (node (ref "P8") (pin "2") (pinfunction "2_2") (pintype "passive"))
      (node (ref "P9") (pin "2") (pinfunction "2_2") (pintype "passive"))
      (node (ref "R15") (pin "1") (pinfunction "1_1") (pintype "passive"))
      (node (ref "R4") (pin "1") (pinfunction "1_1") (pintype "passive"))
      (node (ref "STP1") (pin "4") (pinfunction "GND_4") (pintype "passive"))
      (node (ref "STP2") (pin "4") (pinfunction "GND_4") (pintype "passive"))
      (node (ref "STP3") (pin "4") (pinfunction "GND_4") (pintype "passive"))
      (node (ref "STP4") (pin "4") (pinfunction "GND_4") (pintype "passive"))
      (node (ref "STP5") (pin "4") (pinfunction "GND_4") (pintype "passive"))
      (node (ref "STP6") (pin "4") (pinfunction "GND_4") (pintype "passive"))
      (node (ref "U1") (pin "11") (pinfunction "GND_2_11") (pintype "passive"))
      (node (ref "U1") (pin "32") (pinfunction "GND_4_32") (pintype "passive"))
      (node (ref "U1") (pin "62") (pinfunction "GND_3_62") (pintype "passive"))
      (node (ref "U1") (pin "81") (pinfunction "GND_5_81") (pintype "passive"))
      (node (ref "U1") (pin "99") (pinfunction "GND_99") (pintype "passive"))
      (node (ref "U2") (pin "2") (pinfunction "GND_2") (pintype "passive"))
      (node (ref "U2") (pin "8") (pinfunction "STB_8") (pintype "passive"))
      (node (ref "U3") (pin "10") (pinfunction "VSS_10") (pintype "passive"))
      (node (ref "U5") (pin "1") (pinfunction "GND_1") (pintype "power_in"))
      (node (ref "VR1") (pin "2") (pinfunction "GND_2") (pintype "passive"))
      (node (ref "Y2") (pin "2") (pinfunction "GND_2") (pintype "power_in"))
    )
    (net (code "17") (name "LMT_1") (class "Default")
      (node (ref "P5") (pin "2") (pinfunction "2_2") (pintype "passive"))
      (node (ref "R6") (pin "1") (pinfunction "1_1") (pintype "passive"))
      (node (ref "U1") (pin "78") (pinfunction "PA0_(AD0)_78") (pintype "bidirectional"))
    )
    (net (code "18") (name "LMT_2") (class "Default")
      (node (ref "P6") (pin "2") (pinfunction "2_2") (pintype "passive"))
      (node (ref "R7") (pin "1") (pinfunction "1_1") (pintype "passive"))
      (node (ref "U1") (pin "77") (pinfunction "PA1_(AD1)_77") (pintype "bidirectional"))
    )
    (net (code "19") (name "LMT_3") (class "Default")
      (node (ref "P7") (pin "2") (pinfunction "2_2") (pintype "passive"))
      (node (ref "R8") (pin "1") (pinfunction "1_1") (pintype "passive"))
      (node (ref "U1") (pin "76") (pinfunction "PA2_(AD2)_76") (pintype "bidirectional"))
    )
    (net (code "20") (name "LMT_4") (class "Default")
      (node (ref "P10") (pin "2") (pinfunction "2_2") (pintype "passive"))
      (node (ref "R9") (pin "1") (pinfunction "1_1") (pintype "passive"))
      (node (ref "U1") (pin "75") (pinfunction "PA3_(AD3)_75") (pintype "bidirectional"))
    )
    (net (code "21") (name "LMT_5") (class "Default")
      (node (ref "P15") (pin "2") (pinfunction "2_2") (pintype "passive"))
      (node (ref "R13") (pin "1") (pinfunction "1_1") (pintype "passive"))
      (node (ref "U1") (pin "74") (pinfunction "PA4_(AD4)_74") (pintype "bidirectional"))
    )
    (net (code "22") (name "LMT_6") (class "Default")
      (node (ref "P12") (pin "2") (pinfunction "2_2") (pintype "passive"))
      (node (ref "R10") (pin "1") (pinfunction "1_1") (pintype "passive"))
      (node (ref "U1") (pin "73") (pinfunction "PA5_(AD5)_73") (pintype "bidirectional"))
    )
    (net (code "23") (name "LMT_7") (class "Default")
      (node (ref "P13") (pin "2") (pinfunction "2_2") (pintype "passive"))
      (node (ref "R11") (pin "1") (pinfunction "1_1") (pintype "passive"))
      (node (ref "U1") (pin "72") (pinfunction "PA6_(AD6)_72") (pintype "bidirectional"))
    )
    (net (code "24") (name "LMT_8") (class "Default")
      (node (ref "P14") (pin "2") (pinfunction "2_2") (pintype "passive"))
      (node (ref "R12") (pin "1") (pinfunction "1_1") (pintype "passive"))
      (node (ref "U1") (pin "71") (pinfunction "PA7_(AD7)_71") (pintype "bidirectional"))
    )
    (net (code "25") (name "MISO") (class "Default")
      (node (ref "P1") (pin "2") (pinfunction "2_2") (pintype "passive"))
      (node (ref "P8") (pin "4") (pinfunction "4_4") (pintype "passive"))
      (node (ref "U1") (pin "22") (pinfunction "(MISO/PCINT3)_PB3_22") (pintype "bidirectional"))
    )
    (net (code "26") (name "MOSI") (class "Default")
      (node (ref "P8") (pin "3") (pinfunction "3_3") (pintype "passive"))
      (node (ref "U1") (pin "21") (pinfunction "(MOSI/PCINT2)_PB2_21") (pintype "bidirectional"))
      (node (ref "U3") (pin "16") (pinfunction "SI_16") (pintype "passive"))
    )
    (net (code "27") (name "Net-(CAN1-CANH)") (class "Default")
      (node (ref "CAN1") (pin "1") (pinfunction "CANH_1") (pintype "passive"))
      (node (ref "R3") (pin "2") (pinfunction "2_2") (pintype "passive"))
      (node (ref "U2") (pin "7") (pinfunction "CANH_7") (pintype "passive"))
    )
    (net (code "28") (name "Net-(CAN1-CANL)") (class "Default")
      (node (ref "CAN1") (pin "2") (pinfunction "CANL_2") (pintype "passive"))
      (node (ref "P2") (pin "2") (pinfunction "2_2") (pintype "passive"))
      (node (ref "U2") (pin "6") (pinfunction "CANL_6") (pintype "passive"))
    )
    (net (code "29") (name "Net-(D1-K_(TAB))") (class "Default")
      (node (ref "D1") (pin "4") (pinfunction "K_(TAB)_4") (pintype "passive"))
      (node (ref "L1") (pin "1") (pinfunction "1_1") (pintype "passive"))
      (node (ref "U5") (pin "3") (pinfunction "SW_3") (pintype "passive"))
    )
    (net (code "30") (name "Net-(P2-Pad1)") (class "Default")
      (node (ref "P2") (pin "1") (pinfunction "1_1") (pintype "passive"))
      (node (ref "R3") (pin "1") (pinfunction "1_1") (pintype "passive"))
    )
    (net (code "31") (name "Net-(U2-TXD)") (class "Default")
      (node (ref "U2") (pin "1") (pinfunction "TXD_1") (pintype "passive"))
      (node (ref "U3") (pin "1") (pinfunction "TXCAN_1") (pintype "passive"))
    )
    (net (code "32") (name "Net-(U3-OSC1)") (class "Default")
      (node (ref "C4") (pin "2") (pinfunction "2_2") (pintype "passive"))
      (node (ref "U3") (pin "9") (pinfunction "OSC1_9") (pintype "passive"))
      (node (ref "Y1") (pin "2") (pinfunction "OSC2_2") (pintype "passive"))
    )
    (net (code "33") (name "Net-(U3-OSC2)") (class "Default")
      (node (ref "C7") (pin "1") (pinfunction "1_1") (pintype "passive"))
      (node (ref "U3") (pin "8") (pinfunction "OSC2_8") (pintype "passive"))
      (node (ref "Y1") (pin "1") (pinfunction "OSC1_1") (pintype "passive"))
    )
    (net (code "34") (name "Net-(U3-RESET#)") (class "Default")
      (node (ref "R1") (pin "1") (pinfunction "1_1") (pintype "passive"))
      (node (ref "U3") (pin "19") (pinfunction "RESET#_19") (pintype "passive"))
    )
    (net (code "35") (name "Net-(U3-SO)") (class "Default")
      (node (ref "P1") (pin "1") (pinfunction "1_1") (pintype "passive"))
      (node (ref "U3") (pin "17") (pinfunction "SO_17") (pintype "passive"))
    )
    (net (code "36") (name "Net-(U4-SET)") (class "Default")
      (node (ref "C12") (pin "2") (pinfunction "2_2") (pintype "passive"))
      (node (ref "R4") (pin "2") (pinfunction "2_2") (pintype "passive"))
      (node (ref "U4") (pin "1") (pinfunction "SET_1") (pintype "passive"))
    )
    (net (code "37") (name "Net-(U5-VC)") (class "Default")
      (node (ref "C14") (pin "2") (pinfunction "2_2") (pintype "passive"))
      (node (ref "U5") (pin "4") (pinfunction "VC_4") (pintype "passive"))
    )
    (net (code "38") (name "RX") (class "Default")
      (node (ref "P11") (pin "2") (pinfunction "2_2") (pintype "passive"))
      (node (ref "U1") (pin "2") (pinfunction "(RXD0/PCINT8)_PE0_2") (pintype "bidirectional"))
    )
    (net (code "39") (name "RXCAN") (class "Default")
      (node (ref "U2") (pin "4") (pinfunction "RXD_4") (pintype "passive"))
      (node (ref "U3") (pin "2") (pinfunction "RXCAN_2") (pintype "passive"))
    )
    (net (code "40") (name "SCK") (class "Default")
      (node (ref "P8") (pin "5") (pinfunction "5_5") (pintype "passive"))
      (node (ref "U1") (pin "20") (pinfunction "(SCK/PCINT1)_PB1_20") (pintype "bidirectional"))
      (node (ref "U3") (pin "14") (pinfunction "SCK_14") (pintype "passive"))
    )
    (net (code "41") (name "SERVO_1") (class "Default")
      (node (ref "P3") (pin "2") (pinfunction "2_2") (pintype "passive"))
      (node (ref "U1") (pin "1") (pinfunction "(OC0B)_PG5_1") (pintype "bidirectional"))
    )
    (net (code "42") (name "SERVO_2") (class "Default")
      (node (ref "P4") (pin "2") (pinfunction "2_2") (pintype "passive"))
      (node (ref "U1") (pin "5") (pinfunction "(OC3A/AIN1)_PE3_5") (pintype "bidirectional"))
    )
    (net (code "43") (name "STP1_12V") (class "Default")
      (node (ref "STP1") (pin "2") (pinfunction "STEP_2") (pintype "passive"))
      (node (ref "U1") (pin "23") (pinfunction "(OC2A/PCINT4)_PB4_23") (pintype "bidirectional"))
    )
    (net (code "44") (name "STP1_36V") (class "Default")
      (node (ref "STP2") (pin "2") (pinfunction "STEP_2") (pintype "passive"))
      (node (ref "U1") (pin "55") (pinfunction "PC2_(A10)_55") (pintype "bidirectional"))
    )
    (net (code "45") (name "STP2_12V") (class "Default")
      (node (ref "STP3") (pin "2") (pinfunction "STEP_2") (pintype "passive"))
      (node (ref "U1") (pin "25") (pinfunction "(OC1B/PCINT6)_PB6_25") (pintype "bidirectional"))
    )
    (net (code "46") (name "STP2_36V") (class "Default")
      (node (ref "STP4") (pin "2") (pinfunction "STEP_2") (pintype "passive"))
      (node (ref "U1") (pin "57") (pinfunction "PC4_(A12)_57") (pintype "bidirectional"))
    )
    (net (code "47") (name "STP3_12V") (class "Default")
      (node (ref "STP5") (pin "2") (pinfunction "STEP_2") (pintype "passive"))
      (node (ref "U1") (pin "53") (pinfunction "PC0_(A8)_53") (pintype "bidirectional"))
    )
    (net (code "48") (name "STP3_36V") (class "Default")
      (node (ref "STP6") (pin "2") (pinfunction "STEP_2") (pintype "passive"))
      (node (ref "U1") (pin "59") (pinfunction "PC6_(A14)_59") (pintype "bidirectional"))
    )
    (net (code "49") (name "TCK") (class "Default")
      (node (ref "P9") (pin "6") (pinfunction "6_6") (pintype "passive"))
      (node (ref "U1") (pin "93") (pinfunction "PF4_(ADC4/TCK)_93") (pintype "bidirectional"))
    )
    (net (code "50") (name "TDI") (class "Default")
      (node (ref "P9") (pin "3") (pinfunction "3_3") (pintype "passive"))
      (node (ref "U1") (pin "90") (pinfunction "PF7_(ADC7/TDI)_90") (pintype "bidirectional"))
    )
    (net (code "51") (name "TDO") (class "Default")
      (node (ref "P9") (pin "4") (pinfunction "4_4") (pintype "passive"))
      (node (ref "U1") (pin "91") (pinfunction "PF6_(ADC6/TDO)_91") (pintype "bidirectional"))
    )
    (net (code "52") (name "TMS") (class "Default")
      (node (ref "P9") (pin "5") (pinfunction "5_5") (pintype "passive"))
      (node (ref "U1") (pin "92") (pinfunction "PF5_(ADC5/TMS)_92") (pintype "bidirectional"))
    )
    (net (code "53") (name "TX") (class "Default")
      (node (ref "P11") (pin "3") (pinfunction "3_3") (pintype "passive"))
      (node (ref "U1") (pin "3") (pinfunction "(TXD0)_PE1_3") (pintype "bidirectional"))
    )
    (net (code "54") (name "XTAL1") (class "Default")
      (node (ref "R5") (pin "1") (pinfunction "1_1") (pintype "passive"))
      (node (ref "U1") (pin "34") (pinfunction "XTAL1_34") (pintype "input"))
      (node (ref "Y2") (pin "1") (pinfunction "IN_1") (pintype "passive"))
    )
    (net (code "55") (name "XTAL2") (class "Default")
      (node (ref "R5") (pin "2") (pinfunction "2_2") (pintype "passive"))
      (node (ref "U1") (pin "33") (pinfunction "XTAL2_33") (pintype "output"))
      (node (ref "Y2") (pin "3") (pinfunction "OUT_3") (pintype "passive"))
    )
    (net (code "56") (name "nRESET") (class "Default")
      (node (ref "C5") (pin "1") (pinfunction "1_1") (pintype "passive"))
      (node (ref "P8") (pin "6") (pinfunction "6_6") (pintype "passive"))
      (node (ref "R2") (pin "1") (pinfunction "1_1") (pintype "passive"))
      (node (ref "U1") (pin "30") (pinfunction "~{RESET}_30") (pintype "input"))
    )
    (net (code "57") (name "unconnected-(D1-NOPAD-Pad2)") (class "Default")
      (node (ref "D1") (pin "2") (pinfunction "NOPAD_2") (pintype "passive+no_connect"))
    )
    (net (code "58") (name "unconnected-(U1-(CLKO{slash}ICP3{slash}INT7)_PE7-Pad9)") (class "Default")
      (node (ref "U1") (pin "9") (pinfunction "(CLKO/ICP3/INT7)_PE7_9") (pintype "bidirectional"))
    )
    (net (code "59") (name "unconnected-(U1-(ICP1)_PD4-Pad47)") (class "Default")
      (node (ref "U1") (pin "47") (pinfunction "(ICP1)_PD4_47") (pintype "bidirectional"))
    )
    (net (code "60") (name "unconnected-(U1-(ICP4)_PL0-Pad35)") (class "Default")
      (node (ref "U1") (pin "35") (pinfunction "(ICP4)_PL0_35") (pintype "bidirectional"))
    )
    (net (code "61") (name "unconnected-(U1-(ICP5)_PL1-Pad36)") (class "Default")
      (node (ref "U1") (pin "36") (pinfunction "(ICP5)_PL1_36") (pintype "bidirectional"))
    )
    (net (code "62") (name "unconnected-(U1-(OC2B)_PH6-Pad18)") (class "Default")
      (node (ref "U1") (pin "18") (pinfunction "(OC2B)_PH6_18") (pintype "bidirectional"))
    )
    (net (code "63") (name "unconnected-(U1-(OC3B{slash}INT4)_PE4-Pad6)") (class "Default")
      (node (ref "U1") (pin "6") (pinfunction "(OC3B/INT4)_PE4_6") (pintype "bidirectional"))
    )
    (net (code "64") (name "unconnected-(U1-(OC3C{slash}INT5)_PE5-Pad7)") (class "Default")
      (node (ref "U1") (pin "7") (pinfunction "(OC3C/INT5)_PE5_7") (pintype "bidirectional"))
    )
    (net (code "65") (name "unconnected-(U1-(OC4A)_PH3-Pad15)") (class "Default")
      (node (ref "U1") (pin "15") (pinfunction "(OC4A)_PH3_15") (pintype "bidirectional"))
    )
    (net (code "66") (name "unconnected-(U1-(OC4B)_PH4-Pad16)") (class "Default")
      (node (ref "U1") (pin "16") (pinfunction "(OC4B)_PH4_16") (pintype "bidirectional"))
    )
    (net (code "67") (name "unconnected-(U1-(OC4C)_PH5-Pad17)") (class "Default")
      (node (ref "U1") (pin "17") (pinfunction "(OC4C)_PH5_17") (pintype "bidirectional"))
    )
    (net (code "68") (name "unconnected-(U1-(OC5A)_PL3-Pad38)") (class "Default")
      (node (ref "U1") (pin "38") (pinfunction "(OC5A)_PL3_38") (pintype "bidirectional"))
    )
    (net (code "69") (name "unconnected-(U1-(OC5B)_PL4-Pad39)") (class "Default")
      (node (ref "U1") (pin "39") (pinfunction "(OC5B)_PL4_39") (pintype "bidirectional"))
    )
    (net (code "70") (name "unconnected-(U1-(RXD2)_PH0-Pad12)") (class "Default")
      (node (ref "U1") (pin "12") (pinfunction "(RXD2)_PH0_12") (pintype "bidirectional"))
    )
    (net (code "71") (name "unconnected-(U1-(SCL{slash}INT0)_PD0-Pad43)") (class "Default")
      (node (ref "U1") (pin "43") (pinfunction "(SCL/INT0)_PD0_43") (pintype "bidirectional"))
    )
    (net (code "72") (name "unconnected-(U1-(SDA{slash}INT1)_PD1-Pad44)") (class "Default")
      (node (ref "U1") (pin "44") (pinfunction "(SDA/INT1)_PD1_44") (pintype "bidirectional"))
    )
    (net (code "73") (name "unconnected-(U1-(T0)_PD7-Pad50)") (class "Default")
      (node (ref "U1") (pin "50") (pinfunction "(T0)_PD7_50") (pintype "bidirectional"))
    )
    (net (code "74") (name "unconnected-(U1-(T1)_PD6-Pad49)") (class "Default")
      (node (ref "U1") (pin "49") (pinfunction "(T1)_PD6_49") (pintype "bidirectional"))
    )
    (net (code "75") (name "unconnected-(U1-(T3{slash}INT6)_PE6-Pad8)") (class "Default")
      (node (ref "U1") (pin "8") (pinfunction "(T3/INT6)_PE6_8") (pintype "bidirectional"))
    )
    (net (code "76") (name "unconnected-(U1-(T4)_PH7-Pad27)") (class "Default")
      (node (ref "U1") (pin "27") (pinfunction "(T4)_PH7_27") (pintype "bidirectional"))
    )
    (net (code "77") (name "unconnected-(U1-(T5)_PL2-Pad37)") (class "Default")
      (node (ref "U1") (pin "37") (pinfunction "(T5)_PL2_37") (pintype "bidirectional"))
    )
    (net (code "78") (name "unconnected-(U1-(TOSC1)_PG4-Pad29)") (class "Default")
      (node (ref "U1") (pin "29") (pinfunction "(TOSC1)_PG4_29") (pintype "bidirectional"))
    )
    (net (code "79") (name "unconnected-(U1-(TOSC2)_PG3-Pad28)") (class "Default")
      (node (ref "U1") (pin "28") (pinfunction "(TOSC2)_PG3_28") (pintype "bidirectional"))
    )
    (net (code "80") (name "unconnected-(U1-(TXD1{slash}INT3)_PD3-Pad46)") (class "Default")
      (node (ref "U1") (pin "46") (pinfunction "(TXD1/INT3)_PD3_46") (pintype "bidirectional"))
    )
    (net (code "81") (name "unconnected-(U1-(TXD2)_PH1-Pad13)") (class "Default")
      (node (ref "U1") (pin "13") (pinfunction "(TXD2)_PH1_13") (pintype "bidirectional"))
    )
    (net (code "82") (name "unconnected-(U1-(XCK0{slash}AIN0)_PE2-Pad4)") (class "Default")
      (node (ref "U1") (pin "4") (pinfunction "(XCK0/AIN0)_PE2_4") (pintype "bidirectional"))
    )
    (net (code "83") (name "unconnected-(U1-(XCK1)_PD5-Pad48)") (class "Default")
      (node (ref "U1") (pin "48") (pinfunction "(XCK1)_PD5_48") (pintype "bidirectional"))
    )
    (net (code "84") (name "unconnected-(U1-(XCK2)_PH2-Pad14)") (class "Default")
      (node (ref "U1") (pin "14") (pinfunction "(XCK2)_PH2_14") (pintype "bidirectional"))
    )
    (net (code "85") (name "unconnected-(U1-OC5C)_PL5-Pad40)") (class "Default")
      (node (ref "U1") (pin "40") (pinfunction "OC5C)_PL5_40") (pintype "bidirectional"))
    )
    (net (code "86") (name "unconnected-(U1-PF0_(ADC0)-Pad97)") (class "Default")
      (node (ref "U1") (pin "97") (pinfunction "PF0_(ADC0)_97") (pintype "bidirectional"))
    )
    (net (code "87") (name "unconnected-(U1-PF1_(ADC1)-Pad96)") (class "Default")
      (node (ref "U1") (pin "96") (pinfunction "PF1_(ADC1)_96") (pintype "bidirectional"))
    )
    (net (code "88") (name "unconnected-(U1-PF2_(ADC2)-Pad95)") (class "Default")
      (node (ref "U1") (pin "95") (pinfunction "PF2_(ADC2)_95") (pintype "bidirectional"))
    )
    (net (code "89") (name "unconnected-(U1-PF3_(ADC3)-Pad94)") (class "Default")
      (node (ref "U1") (pin "94") (pinfunction "PF3_(ADC3)_94") (pintype "bidirectional"))
    )
    (net (code "90") (name "unconnected-(U1-PG0_(~WR)-Pad51)") (class "Default")
      (node (ref "U1") (pin "51") (pinfunction "PG0_(~WR)_51") (pintype "bidirectional"))
    )
    (net (code "91") (name "unconnected-(U1-PG1_(~RD)-Pad52)") (class "Default")
      (node (ref "U1") (pin "52") (pinfunction "PG1_(~RD)_52") (pintype "bidirectional"))
    )
    (net (code "92") (name "unconnected-(U1-PG2_(ALE)-Pad70)") (class "Default")
      (node (ref "U1") (pin "70") (pinfunction "PG2_(ALE)_70") (pintype "bidirectional"))
    )
    (net (code "93") (name "unconnected-(U1-PJ0_(RXD3{slash}PCINT9)-Pad63)") (class "Default")
      (node (ref "U1") (pin "63") (pinfunction "PJ0_(RXD3/PCINT9)_63") (pintype "bidirectional"))
    )
    (net (code "94") (name "unconnected-(U1-PJ1_(TXD3{slash}PCINT10)-Pad64)") (class "Default")
      (node (ref "U1") (pin "64") (pinfunction "PJ1_(TXD3/PCINT10)_64") (pintype "bidirectional"))
    )
    (net (code "95") (name "unconnected-(U1-PJ2_(XCK3{slash}PCINT11)-Pad65)") (class "Default")
      (node (ref "U1") (pin "65") (pinfunction "PJ2_(XCK3/PCINT11)_65") (pintype "bidirectional"))
    )
    (net (code "96") (name "unconnected-(U1-PJ3_(PCINT12)-Pad66)") (class "Default")
      (node (ref "U1") (pin "66") (pinfunction "PJ3_(PCINT12)_66") (pintype "bidirectional"))
    )
    (net (code "97") (name "unconnected-(U1-PJ4_(PCINT13)-Pad67)") (class "Default")
      (node (ref "U1") (pin "67") (pinfunction "PJ4_(PCINT13)_67") (pintype "bidirectional"))
    )
    (net (code "98") (name "unconnected-(U1-PJ5_(PCINT14)-Pad68)") (class "Default")
      (node (ref "U1") (pin "68") (pinfunction "PJ5_(PCINT14)_68") (pintype "bidirectional"))
    )
    (net (code "99") (name "unconnected-(U1-PJ6_(PCINT15)-Pad69)") (class "Default")
      (node (ref "U1") (pin "69") (pinfunction "PJ6_(PCINT15)_69") (pintype "bidirectional"))
    )
    (net (code "100") (name "unconnected-(U1-PJ7-Pad79)") (class "Default")
      (node (ref "U1") (pin "79") (pinfunction "PJ7_79") (pintype "bidirectional"))
    )
    (net (code "101") (name "unconnected-(U1-PK0_(ADC8{slash}PCINT16)-Pad89)") (class "Default")
      (node (ref "U1") (pin "89") (pinfunction "PK0_(ADC8/PCINT16)_89") (pintype "bidirectional"))
    )
    (net (code "102") (name "unconnected-(U1-PK1_(ADC9{slash}PCINT17)-Pad88)") (class "Default")
      (node (ref "U1") (pin "88") (pinfunction "PK1_(ADC9/PCINT17)_88") (pintype "bidirectional"))
    )
    (net (code "103") (name "unconnected-(U1-PK2_(ADC10{slash}PCINT18)-Pad87)") (class "Default")
      (node (ref "U1") (pin "87") (pinfunction "PK2_(ADC10/PCINT18)_87") (pintype "bidirectional"))
    )
    (net (code "104") (name "unconnected-(U1-PK3_(ADC11{slash}PCINT19)-Pad86)") (class "Default")
      (node (ref "U1") (pin "86") (pinfunction "PK3_(ADC11/PCINT19)_86") (pintype "bidirectional"))
    )
    (net (code "105") (name "unconnected-(U1-PK4_(ADC12{slash}PCINT20)-Pad85)") (class "Default")
      (node (ref "U1") (pin "85") (pinfunction "PK4_(ADC12/PCINT20)_85") (pintype "bidirectional"))
    )
    (net (code "106") (name "unconnected-(U1-PK5_(ADC13{slash}PCINT21)-Pad84)") (class "Default")
      (node (ref "U1") (pin "84") (pinfunction "PK5_(ADC13/PCINT21)_84") (pintype "bidirectional"))
    )
    (net (code "107") (name "unconnected-(U1-PK6_(ADC14{slash}PCINT22)-Pad83)") (class "Default")
      (node (ref "U1") (pin "83") (pinfunction "PK6_(ADC14/PCINT22)_83") (pintype "bidirectional"))
    )
    (net (code "108") (name "unconnected-(U1-PK7_(ADC15{slash}PCINT23)-Pad82)") (class "Default")
      (node (ref "U1") (pin "82") (pinfunction "PK7_(ADC15/PCINT23)_82") (pintype "bidirectional"))
    )
    (net (code "109") (name "unconnected-(U1-PL6-Pad41)") (class "Default")
      (node (ref "U1") (pin "41") (pinfunction "PL6_41") (pintype "bidirectional"))
    )
    (net (code "110") (name "unconnected-(U1-PL7-Pad42)") (class "Default")
      (node (ref "U1") (pin "42") (pinfunction "PL7_42") (pintype "bidirectional"))
    )
    (net (code "111") (name "unconnected-(U2-SPLIT-Pad5)") (class "Default")
      (node (ref "U2") (pin "5") (pinfunction "SPLIT_5") (pintype "passive+no_connect"))
    )
    (net (code "112") (name "unconnected-(U3-CLKOUT{slash}SOF-Pad3)") (class "Default")
      (node (ref "U3") (pin "3") (pinfunction "CLKOUT/SOF_3") (pintype "passive"))
    )
    (net (code "113") (name "unconnected-(U3-NC-Pad6)") (class "Default")
      (node (ref "U3") (pin "6") (pinfunction "NC_6") (pintype "passive+no_connect"))
    )
    (net (code "114") (name "unconnected-(U3-NC-Pad15)") (class "Default")
      (node (ref "U3") (pin "15") (pinfunction "NC_15") (pintype "passive+no_connect"))
    )
    (net (code "115") (name "unconnected-(U3-RX0BF#-Pad12)") (class "Default")
      (node (ref "U3") (pin "12") (pinfunction "RX0BF#_12") (pintype "passive"))
    )
    (net (code "116") (name "unconnected-(U3-RX1BF#-Pad11)") (class "Default")
      (node (ref "U3") (pin "11") (pinfunction "RX1BF#_11") (pintype "passive"))
    )
    (net (code "117") (name "unconnected-(U3-TX0RTS#-Pad4)") (class "Default")
      (node (ref "U3") (pin "4") (pinfunction "TX0RTS#_4") (pintype "passive"))
    )
    (net (code "118") (name "unconnected-(U3-TX1RTS#-Pad5)") (class "Default")
      (node (ref "U3") (pin "5") (pinfunction "TX1RTS#_5") (pintype "passive"))
    )
    (net (code "119") (name "unconnected-(U3-TX2RTS#-Pad7)") (class "Default")
      (node (ref "U3") (pin "7") (pinfunction "TX2RTS#_7") (pintype "passive"))
    )
  )
)
